# T06_LockBox.net
KiCad netlist of a schematic drawn in EAGLE
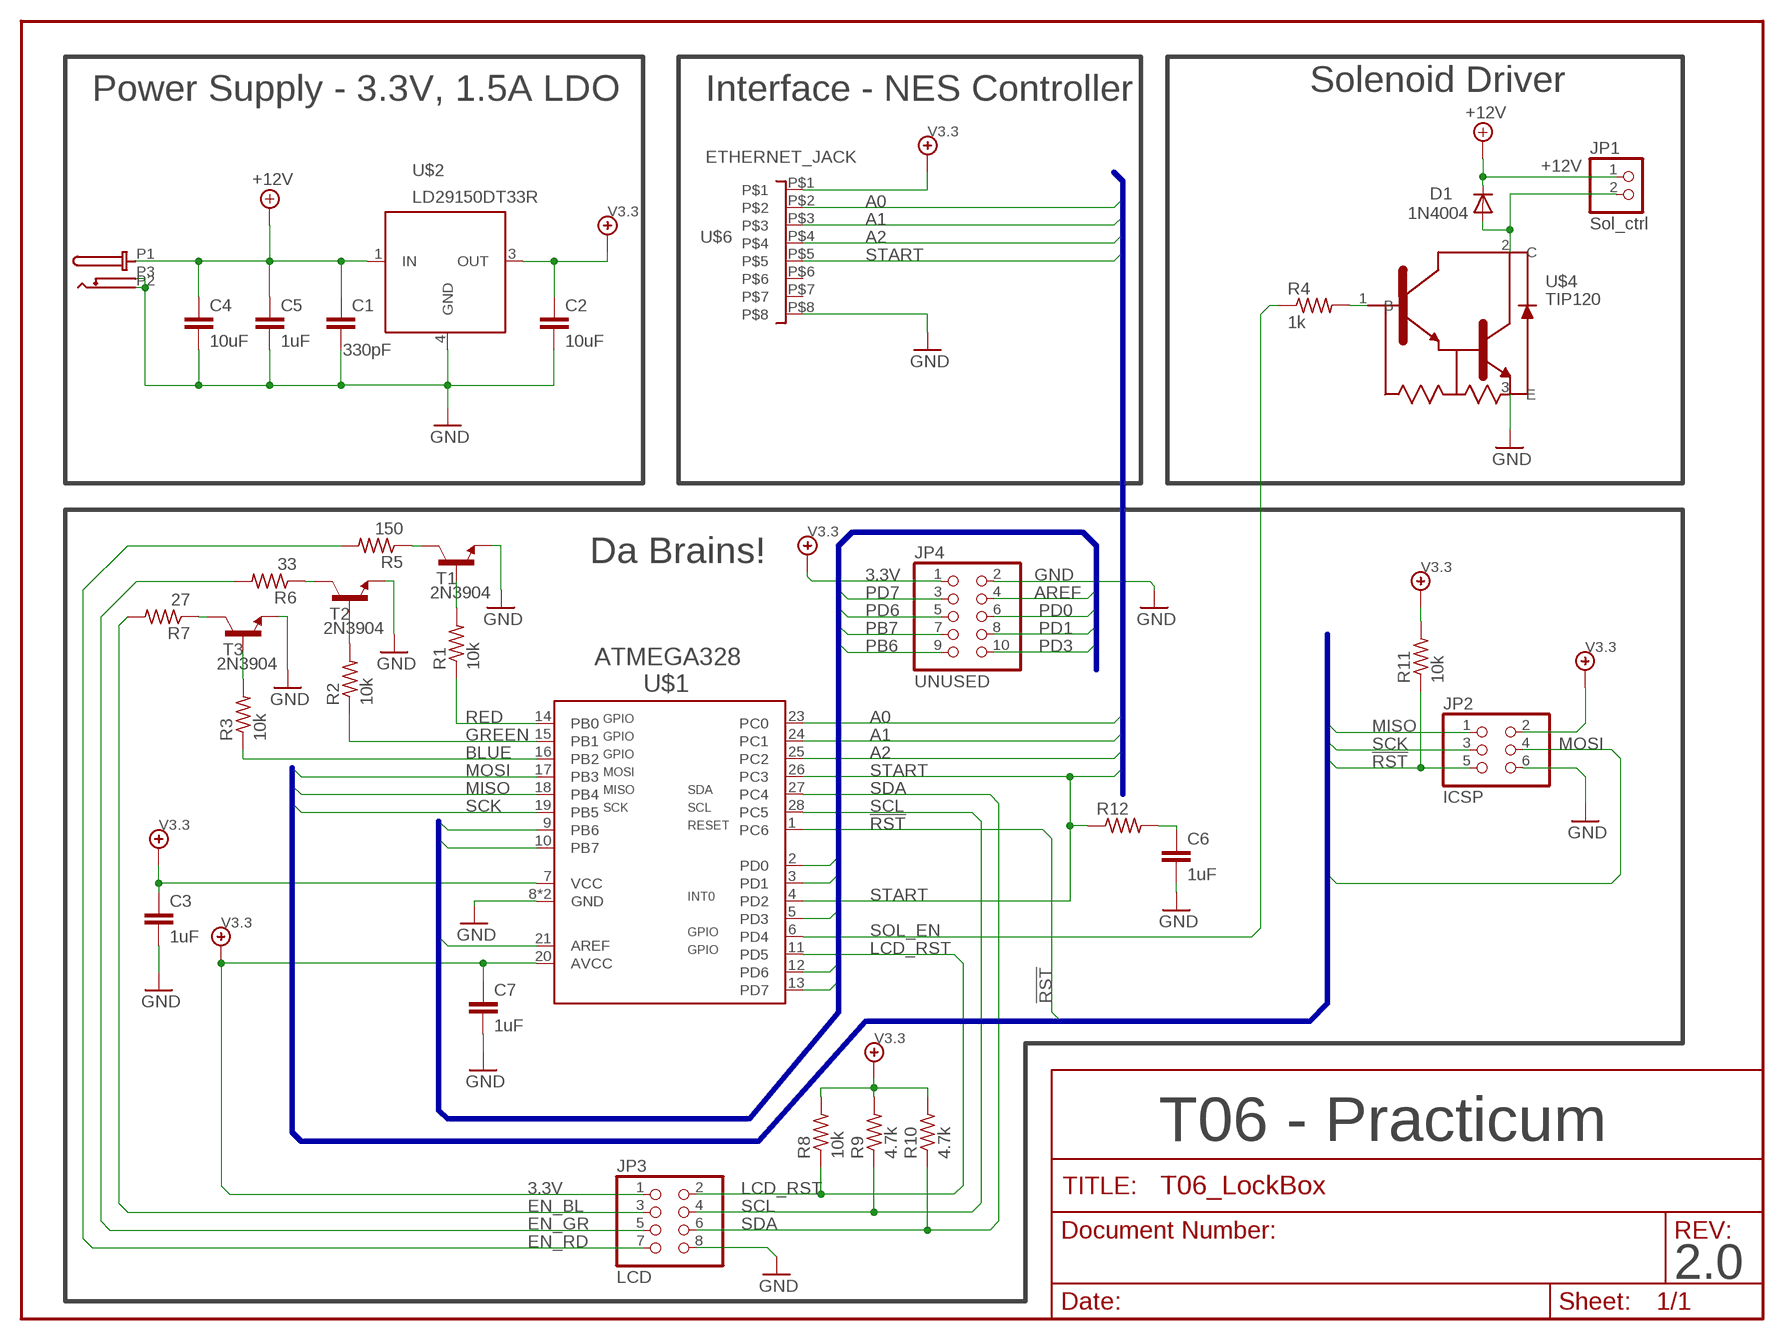
[diagram p0: schematic, sheet 1]

(export (version "E")
  (design (tool "Eeschema 10.0.6"))
  (components
    (comp (ref "C1")
      (value "330pF")
      (footprint "eagle-import:C0805")
      (libsource (lib "eagle-import") (part "C"))
    )
    (comp (ref "C2")
      (value "10uF")
      (footprint "eagle-import:C0805")
      (libsource (lib "eagle-import") (part "C"))
    )
    (comp (ref "C3")
      (value "1uF")
      (footprint "eagle-import:C0805")
      (libsource (lib "eagle-import") (part "C"))
    )
    (comp (ref "C4")
      (value "10uF")
      (footprint "eagle-import:C1206")
      (libsource (lib "eagle-import") (part "CC1206"))
    )
    (comp (ref "C5")
      (value "1uF")
      (footprint "eagle-import:C0805")
      (libsource (lib "eagle-import") (part "C"))
    )
    (comp (ref "C6")
      (value "1uF")
      (footprint "eagle-import:C0805")
      (libsource (lib "eagle-import") (part "C"))
    )
    (comp (ref "C7")
      (value "1uF")
      (footprint "eagle-import:C0805")
      (libsource (lib "eagle-import") (part "C"))
    )
    (comp (ref "D1")
      (value "1N4004")
      (footprint "eagle-import:DO41-10")
      (libsource (lib "eagle-import") (part "1N4004"))
    )
    (comp (ref "JP1")
      (value "Sol_ctrl")
      (footprint "eagle-import:1X02")
      (libsource (lib "eagle-import") (part "PINHD-1X2"))
    )
    (comp (ref "JP2")
      (value "ICSP")
      (footprint "eagle-import:2X03")
      (libsource (lib "eagle-import") (part "PINHD-2X3"))
    )
    (comp (ref "JP3")
      (value "LCD")
      (footprint "eagle-import:2X04")
      (libsource (lib "eagle-import") (part "PINHD-2X4"))
    )
    (comp (ref "JP4")
      (value "UNUSED")
      (footprint "eagle-import:2X05")
      (libsource (lib "eagle-import") (part "PINHD-2X5"))
    )
    (comp (ref "R1")
      (value "10k")
      (footprint "eagle-import:R0805")
      (libsource (lib "eagle-import") (part "R-US_R0805"))
    )
    (comp (ref "R2")
      (value "10k")
      (footprint "eagle-import:R0805")
      (libsource (lib "eagle-import") (part "R-US_R0805"))
    )
    (comp (ref "R3")
      (value "10k")
      (footprint "eagle-import:R0805")
      (libsource (lib "eagle-import") (part "R-US_R0805"))
    )
    (comp (ref "R4")
      (value "1k")
      (footprint "eagle-import:M0805")
      (libsource (lib "eagle-import") (part "R-US_M0805"))
    )
    (comp (ref "R5")
      (value "150")
      (footprint "eagle-import:R0805")
      (libsource (lib "eagle-import") (part "R-US_R0805"))
    )
    (comp (ref "R6")
      (value "33")
      (footprint "eagle-import:R0805")
      (libsource (lib "eagle-import") (part "R-US_R0805"))
    )
    (comp (ref "R7")
      (value "27")
      (footprint "eagle-import:R0805")
      (libsource (lib "eagle-import") (part "R-US_R0805"))
    )
    (comp (ref "R8")
      (value "10k")
      (footprint "eagle-import:R0805")
      (libsource (lib "eagle-import") (part "R-US_R0805"))
    )
    (comp (ref "R9")
      (value "4.7k")
      (footprint "eagle-import:R0805")
      (libsource (lib "eagle-import") (part "R-US_R0805"))
    )
    (comp (ref "R10")
      (value "4.7k")
      (footprint "eagle-import:R0805")
      (libsource (lib "eagle-import") (part "R-US_R0805"))
    )
    (comp (ref "R11")
      (value "10k")
      (footprint "eagle-import:M0805")
      (libsource (lib "eagle-import") (part "R-US_M0805"))
    )
    (comp (ref "R12")
      (value "R-US_M0805")
      (footprint "eagle-import:M0805")
      (libsource (lib "eagle-import") (part "R-US_M0805"))
    )
    (comp (ref "T1")
      (value "2N3904")
      (footprint "eagle-import:TO92-BCE")
      (libsource (lib "eagle-import") (part "2N3904"))
    )
    (comp (ref "T2")
      (value "2N3904")
      (footprint "eagle-import:TO92-BCE")
      (libsource (lib "eagle-import") (part "2N3904"))
    )
    (comp (ref "T3")
      (value "2N3904")
      (footprint "eagle-import:TO92-BCE")
      (libsource (lib "eagle-import") (part "2N3904"))
    )
    (comp (ref "U$1")
      (value "ATMEGA328")
      (footprint "eagle-import:DIL28-3")
      (fields
        (field (name "PB0") "GPIO")
        (field (name "PB1") "GPIO")
        (field (name "PB2") "GPIO")
        (field (name "PB3") "MOSI")
        (field (name "PB4") "MISO")
        (field (name "PB5") "SCK")
        (field (name "PC4") "SDA")
        (field (name "PC5") "SCL")
        (field (name "PC6") "RESET")
        (field (name "PD2") "INT0")
        (field (name "PD4") "GPIO")
        (field (name "PD5") "GPIO")
      )
      (libsource (lib "eagle-import") (part "ATMEGA328"))
    )
    (comp (ref "U$2")
      (value "LD29150DT33R")
      (footprint "eagle-import:DPAK")
      (libsource (lib "eagle-import") (part "LD29150DT33R"))
    )
    (comp (ref "U$3")
      (value "PJ-102A")
      (footprint "eagle-import:PJ-102A")
      (libsource (lib "eagle-import") (part "PJ-102A"))
    )
    (comp (ref "U$4")
      (value "TIP120")
      (footprint "eagle-import:T0220-3")
      (fields (field (name "MFG") "Fairchild"))
      (libsource (lib "eagle-import") (part "TIP120"))
    )
    (comp (ref "U$6")
      (value "ETHERNET_JACK")
      (footprint "eagle-import:MODJACK8")
      (libsource (lib "eagle-import") (part "ETHERNET_JACK"))
    )
  )
  (nets
    (net (code "1") (name "+12V") (class "Default")
      (node (ref "C1") (pin "1") (pinfunction "1_1") (pintype "passive"))
      (node (ref "C4") (pin "1") (pinfunction "1_1") (pintype "passive"))
      (node (ref "C5") (pin "1") (pinfunction "1_1") (pintype "passive"))
      (node (ref "D1") (pin "C") (pinfunction "C_C") (pintype "passive"))
      (node (ref "JP1") (pin "1") (pinfunction "1_1") (pintype "passive"))
      (node (ref "U$2") (pin "1") (pinfunction "IN_1") (pintype "bidirectional"))
      (node (ref "U$3") (pin "P1") (pinfunction "PWR_P1") (pintype "power_in"))
    )
    (net (code "2") (name "/A0") (class "Default")
      (node (ref "U$1") (pin "23") (pinfunction "PC0_23") (pintype "bidirectional"))
      (node (ref "U$6") (pin "P$2") (pinfunction "P$2_P$2") (pintype "bidirectional"))
    )
    (net (code "3") (name "/A1") (class "Default")
      (node (ref "U$1") (pin "24") (pinfunction "PC1_24") (pintype "bidirectional"))
      (node (ref "U$6") (pin "P$3") (pinfunction "P$3_P$3") (pintype "bidirectional"))
    )
    (net (code "4") (name "/A2") (class "Default")
      (node (ref "U$1") (pin "25") (pinfunction "PC2_25") (pintype "bidirectional"))
      (node (ref "U$6") (pin "P$4") (pinfunction "P$4_P$4") (pintype "bidirectional"))
    )
    (net (code "5") (name "/AREF") (class "Default")
      (node (ref "JP4") (pin "4") (pinfunction "4_4") (pintype "passive"))
      (node (ref "U$1") (pin "21") (pinfunction "AREF_21") (pintype "power_in"))
    )
    (net (code "6") (name "/BLUE") (class "Default")
      (node (ref "R3") (pin "1") (pinfunction "1_1") (pintype "passive"))
      (node (ref "U$1") (pin "16") (pinfunction "PB2_16") (pintype "bidirectional"))
    )
    (net (code "7") (name "/EN_BL") (class "Default")
      (node (ref "JP3") (pin "3") (pinfunction "3_3") (pintype "passive"))
      (node (ref "R7") (pin "2") (pinfunction "2_2") (pintype "passive"))
    )
    (net (code "8") (name "/EN_GR") (class "Default")
      (node (ref "JP3") (pin "5") (pinfunction "5_5") (pintype "passive"))
      (node (ref "R6") (pin "2") (pinfunction "2_2") (pintype "passive"))
    )
    (net (code "9") (name "/EN_RD") (class "Default")
      (node (ref "JP3") (pin "7") (pinfunction "7_7") (pintype "passive"))
      (node (ref "R5") (pin "2") (pinfunction "2_2") (pintype "passive"))
    )
    (net (code "10") (name "/GREEN") (class "Default")
      (node (ref "R2") (pin "1") (pinfunction "1_1") (pintype "passive"))
      (node (ref "U$1") (pin "15") (pinfunction "PB1_15") (pintype "bidirectional"))
    )
    (net (code "11") (name "/LCD_RST") (class "Default")
      (node (ref "JP3") (pin "2") (pinfunction "2_2") (pintype "passive"))
      (node (ref "R8") (pin "1") (pinfunction "1_1") (pintype "passive"))
      (node (ref "U$1") (pin "11") (pinfunction "PD5_11") (pintype "bidirectional"))
    )
    (net (code "12") (name "/MISO") (class "Default")
      (node (ref "JP2") (pin "1") (pinfunction "1_1") (pintype "passive"))
      (node (ref "U$1") (pin "18") (pinfunction "PB4_18") (pintype "bidirectional"))
    )
    (net (code "13") (name "/MOSI") (class "Default")
      (node (ref "JP2") (pin "4") (pinfunction "4_4") (pintype "passive"))
      (node (ref "U$1") (pin "17") (pinfunction "PB3_17") (pintype "bidirectional"))
    )
    (net (code "14") (name "/PB6") (class "Default")
      (node (ref "JP4") (pin "9") (pinfunction "9_9") (pintype "passive"))
      (node (ref "U$1") (pin "9") (pinfunction "PB6_9") (pintype "bidirectional"))
    )
    (net (code "15") (name "/PB7") (class "Default")
      (node (ref "JP4") (pin "7") (pinfunction "7_7") (pintype "passive"))
      (node (ref "U$1") (pin "10") (pinfunction "PB7_10") (pintype "bidirectional"))
    )
    (net (code "16") (name "/PD0") (class "Default")
      (node (ref "JP4") (pin "6") (pinfunction "6_6") (pintype "passive"))
      (node (ref "U$1") (pin "2") (pinfunction "PD0_2") (pintype "bidirectional"))
    )
    (net (code "17") (name "/PD1") (class "Default")
      (node (ref "JP4") (pin "8") (pinfunction "8_8") (pintype "passive"))
      (node (ref "U$1") (pin "3") (pinfunction "PD1_3") (pintype "bidirectional"))
    )
    (net (code "18") (name "/PD3") (class "Default")
      (node (ref "JP4") (pin "10") (pinfunction "10_10") (pintype "passive"))
      (node (ref "U$1") (pin "5") (pinfunction "PD3_5") (pintype "bidirectional"))
    )
    (net (code "19") (name "/PD6") (class "Default")
      (node (ref "JP4") (pin "5") (pinfunction "5_5") (pintype "passive"))
      (node (ref "U$1") (pin "12") (pinfunction "PD6_12") (pintype "bidirectional"))
    )
    (net (code "20") (name "/PD7") (class "Default")
      (node (ref "JP4") (pin "3") (pinfunction "3_3") (pintype "passive"))
      (node (ref "U$1") (pin "13") (pinfunction "PD7_13") (pintype "bidirectional"))
    )
    (net (code "21") (name "/RED") (class "Default")
      (node (ref "R1") (pin "1") (pinfunction "1_1") (pintype "passive"))
      (node (ref "U$1") (pin "14") (pinfunction "PB0_14") (pintype "bidirectional"))
    )
    (net (code "22") (name "/SCK") (class "Default")
      (node (ref "JP2") (pin "3") (pinfunction "3_3") (pintype "passive"))
      (node (ref "U$1") (pin "19") (pinfunction "PB5_19") (pintype "bidirectional"))
    )
    (net (code "23") (name "/SCL") (class "Default")
      (node (ref "JP3") (pin "4") (pinfunction "4_4") (pintype "passive"))
      (node (ref "R9") (pin "1") (pinfunction "1_1") (pintype "passive"))
      (node (ref "U$1") (pin "28") (pinfunction "PC5_28") (pintype "bidirectional"))
    )
    (net (code "24") (name "/SDA") (class "Default")
      (node (ref "JP3") (pin "6") (pinfunction "6_6") (pintype "passive"))
      (node (ref "R10") (pin "1") (pinfunction "1_1") (pintype "passive"))
      (node (ref "U$1") (pin "27") (pinfunction "PC4_27") (pintype "bidirectional"))
    )
    (net (code "25") (name "/SOL_EN") (class "Default")
      (node (ref "R4") (pin "1") (pinfunction "1_1") (pintype "passive"))
      (node (ref "U$1") (pin "6") (pinfunction "PD4_6") (pintype "bidirectional"))
    )
    (net (code "26") (name "/START") (class "Default")
      (node (ref "R12") (pin "1") (pinfunction "1_1") (pintype "passive"))
      (node (ref "U$1") (pin "26") (pinfunction "PC3_26") (pintype "bidirectional"))
      (node (ref "U$1") (pin "4") (pinfunction "PD2_4") (pintype "bidirectional"))
      (node (ref "U$6") (pin "P$5") (pinfunction "P$5_P$5") (pintype "bidirectional"))
    )
    (net (code "27") (name "/~{RST}") (class "Default")
      (node (ref "JP2") (pin "5") (pinfunction "5_5") (pintype "passive"))
      (node (ref "R11") (pin "1") (pinfunction "1_1") (pintype "passive"))
      (node (ref "U$1") (pin "1") (pinfunction "PC6_1") (pintype "bidirectional"))
    )
    (net (code "28") (name "GND") (class "Default")
      (node (ref "C1") (pin "2") (pinfunction "2_2") (pintype "passive"))
      (node (ref "C2") (pin "2") (pinfunction "2_2") (pintype "passive"))
      (node (ref "C3") (pin "2") (pinfunction "2_2") (pintype "passive"))
      (node (ref "C4") (pin "2") (pinfunction "2_2") (pintype "passive"))
      (node (ref "C5") (pin "2") (pinfunction "2_2") (pintype "passive"))
      (node (ref "C6") (pin "2") (pinfunction "2_2") (pintype "passive"))
      (node (ref "C7") (pin "2") (pinfunction "2_2") (pintype "passive"))
      (node (ref "JP2") (pin "6") (pinfunction "6_6") (pintype "passive"))
      (node (ref "JP3") (pin "8") (pinfunction "8_8") (pintype "passive"))
      (node (ref "JP4") (pin "2") (pinfunction "2_2") (pintype "passive"))
      (node (ref "T1") (pin "E") (pinfunction "E_E") (pintype "passive"))
      (node (ref "T2") (pin "E") (pinfunction "E_E") (pintype "passive"))
      (node (ref "T3") (pin "E") (pinfunction "E_E") (pintype "passive"))
      (node (ref "U$1") (pin "22") (pinfunction "GND_22") (pintype "power_in"))
      (node (ref "U$1") (pin "8") (pinfunction "GND_8") (pintype "power_in"))
      (node (ref "U$2") (pin "4") (pinfunction "GND_4") (pintype "bidirectional"))
      (node (ref "U$3") (pin "P2") (pinfunction "GND_P2") (pintype "power_in"))
      (node (ref "U$3") (pin "P3") (pinfunction "GND_P3") (pintype "power_in"))
      (node (ref "U$4") (pin "3") (pinfunction "E_3") (pintype "bidirectional"))
      (node (ref "U$6") (pin "P$8") (pinfunction "P$8_P$8") (pintype "bidirectional"))
    )
    (net (code "29") (name "Net-(C6-Pad1)") (class "Default")
      (node (ref "C6") (pin "1") (pinfunction "1_1") (pintype "passive"))
      (node (ref "R12") (pin "2") (pinfunction "2_2") (pintype "passive"))
    )
    (net (code "30") (name "Net-(R1-Pad2)") (class "Default")
      (node (ref "R1") (pin "2") (pinfunction "2_2") (pintype "passive"))
      (node (ref "T1") (pin "B") (pinfunction "B_B") (pintype "passive"))
    )
    (net (code "31") (name "Net-(R2-Pad2)") (class "Default")
      (node (ref "R2") (pin "2") (pinfunction "2_2") (pintype "passive"))
      (node (ref "T2") (pin "B") (pinfunction "B_B") (pintype "passive"))
    )
    (net (code "32") (name "Net-(R3-Pad2)") (class "Default")
      (node (ref "R3") (pin "2") (pinfunction "2_2") (pintype "passive"))
      (node (ref "T3") (pin "B") (pinfunction "B_B") (pintype "passive"))
    )
    (net (code "33") (name "Net-(R5-Pad1)") (class "Default")
      (node (ref "R5") (pin "1") (pinfunction "1_1") (pintype "passive"))
      (node (ref "T1") (pin "C") (pinfunction "C_C") (pintype "passive"))
    )
    (net (code "34") (name "Net-(R6-Pad1)") (class "Default")
      (node (ref "R6") (pin "1") (pinfunction "1_1") (pintype "passive"))
      (node (ref "T2") (pin "C") (pinfunction "C_C") (pintype "passive"))
    )
    (net (code "35") (name "Net-(R7-Pad1)") (class "Default")
      (node (ref "R7") (pin "1") (pinfunction "1_1") (pintype "passive"))
      (node (ref "T3") (pin "C") (pinfunction "C_C") (pintype "passive"))
    )
    (net (code "36") (name "Net-(U$4-B)") (class "Default")
      (node (ref "R4") (pin "2") (pinfunction "2_2") (pintype "passive"))
      (node (ref "U$4") (pin "1") (pinfunction "B_1") (pintype "bidirectional"))
    )
    (net (code "37") (name "Net-(U$4-C)") (class "Default")
      (node (ref "D1") (pin "A") (pinfunction "A_A") (pintype "passive"))
      (node (ref "JP1") (pin "2") (pinfunction "2_2") (pintype "passive"))
      (node (ref "U$4") (pin "2") (pinfunction "C_2") (pintype "bidirectional"))
    )
    (net (code "38") (name "V3.3") (class "Default")
      (node (ref "C2") (pin "1") (pinfunction "1_1") (pintype "passive"))
      (node (ref "C3") (pin "1") (pinfunction "1_1") (pintype "passive"))
      (node (ref "C7") (pin "1") (pinfunction "1_1") (pintype "passive"))
      (node (ref "JP2") (pin "2") (pinfunction "2_2") (pintype "passive"))
      (node (ref "JP3") (pin "1") (pinfunction "1_1") (pintype "passive"))
      (node (ref "JP4") (pin "1") (pinfunction "1_1") (pintype "passive"))
      (node (ref "R10") (pin "2") (pinfunction "2_2") (pintype "passive"))
      (node (ref "R11") (pin "2") (pinfunction "2_2") (pintype "passive"))
      (node (ref "R8") (pin "2") (pinfunction "2_2") (pintype "passive"))
      (node (ref "R9") (pin "2") (pinfunction "2_2") (pintype "passive"))
      (node (ref "U$1") (pin "20") (pinfunction "AVCC_20") (pintype "power_in"))
      (node (ref "U$1") (pin "7") (pinfunction "VCC_7") (pintype "power_in"))
      (node (ref "U$2") (pin "3") (pinfunction "OUT_3") (pintype "bidirectional"))
      (node (ref "U$6") (pin "P$1") (pinfunction "P$1_P$1") (pintype "bidirectional"))
    )
    (net (code "39") (name "unconnected-(U$6-PadP$6)") (class "Default")
      (node (ref "U$6") (pin "P$6") (pinfunction "P$6_P$6") (pintype "bidirectional"))
    )
    (net (code "40") (name "unconnected-(U$6-PadP$7)") (class "Default")
      (node (ref "U$6") (pin "P$7") (pinfunction "P$7_P$7") (pintype "bidirectional"))
    )
  )
)
